# Power_Supply_LV.net
KiCad netlist of a schematic drawn in Altium Designer
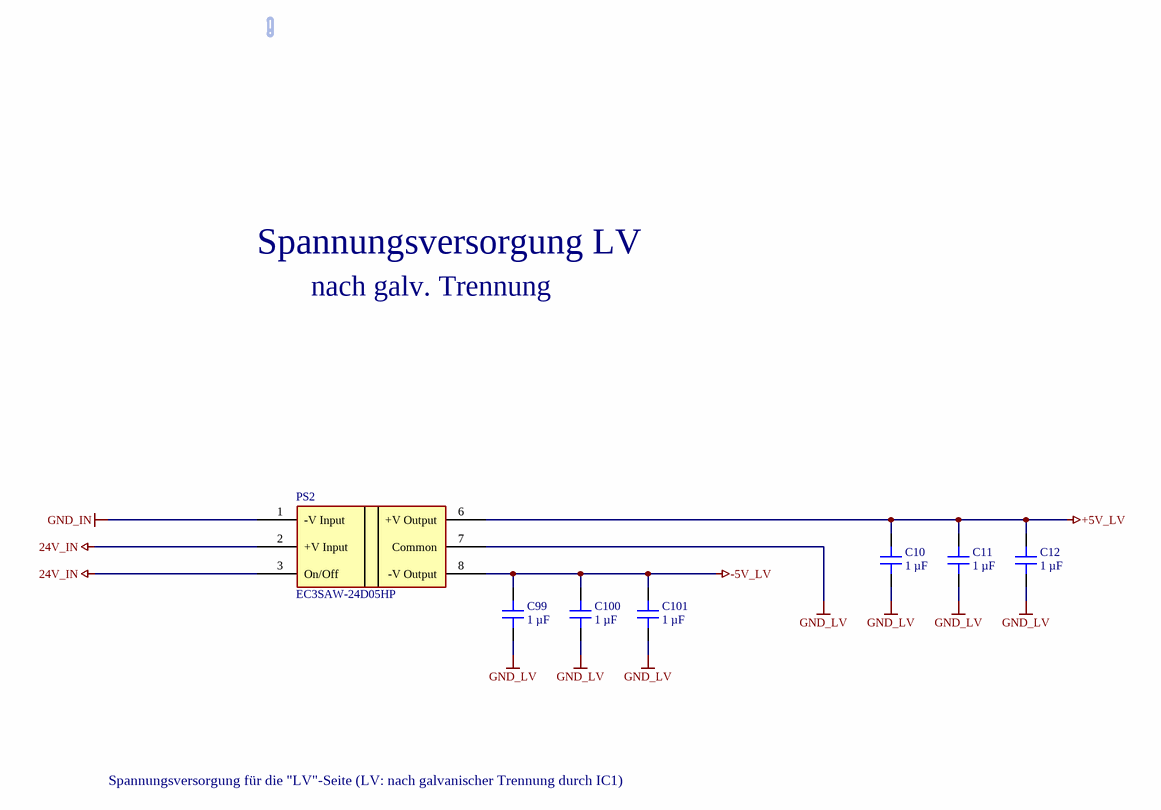
[diagram p0: Power_Supply_LV.SchDoc]

(export (version "E")
  (design (tool "Eeschema 10.0.6"))
  (components
    (comp (ref "C10")
      (value "1 µF")
      (footprint "C_0603")
      (description "50V 1uF X5R ±10% 0603  Multilayer Ceramic Capacitors MLCC - SMD/SMT ROHS")
      (fields
        (field (name "MANUFACTURER") "Samsung Electro-Mechanics")
        (field (name "MANUFACTURER PART NUMBER") "CL10A105KB8NNNC")
        (field (name "CREATED FROM") "MGremer")
      )
      (libsource (lib "user") (part "Capacitor"))
    )
    (comp (ref "C11")
      (value "1 µF")
      (footprint "C_0603")
      (description "50V 1uF X5R ±10% 0603  Multilayer Ceramic Capacitors MLCC - SMD/SMT ROHS")
      (fields
        (field (name "MANUFACTURER") "Samsung Electro-Mechanics")
        (field (name "MANUFACTURER PART NUMBER") "CL10A105KB8NNNC")
        (field (name "CREATED FROM") "MGremer")
      )
      (libsource (lib "user") (part "Capacitor"))
    )
    (comp (ref "C12")
      (value "1 µF")
      (footprint "C_0603")
      (description "50V 1uF X5R ±10% 0603  Multilayer Ceramic Capacitors MLCC - SMD/SMT ROHS")
      (fields
        (field (name "MANUFACTURER") "Samsung Electro-Mechanics")
        (field (name "MANUFACTURER PART NUMBER") "CL10A105KB8NNNC")
        (field (name "CREATED FROM") "MGremer")
      )
      (libsource (lib "user") (part "Capacitor"))
    )
    (comp (ref "C99")
      (value "1 µF")
      (footprint "C_0603")
      (description "50V 1uF X5R ±10% 0603  Multilayer Ceramic Capacitors MLCC - SMD/SMT ROHS")
      (fields
        (field (name "MANUFACTURER") "Samsung Electro-Mechanics")
        (field (name "MANUFACTURER PART NUMBER") "CL10A105KB8NNNC")
        (field (name "CREATED FROM") "MGremer")
      )
      (libsource (lib "user") (part "Capacitor"))
    )
    (comp (ref "C100")
      (value "1 µF")
      (footprint "C_0603")
      (description "50V 1uF X5R ±10% 0603  Multilayer Ceramic Capacitors MLCC - SMD/SMT ROHS")
      (fields
        (field (name "MANUFACTURER") "Samsung Electro-Mechanics")
        (field (name "MANUFACTURER PART NUMBER") "CL10A105KB8NNNC")
        (field (name "CREATED FROM") "MGremer")
      )
      (libsource (lib "user") (part "Capacitor"))
    )
    (comp (ref "C101")
      (value "1 µF")
      (footprint "C_0603")
      (description "50V 1uF X5R ±10% 0603  Multilayer Ceramic Capacitors MLCC - SMD/SMT ROHS")
      (fields
        (field (name "MANUFACTURER") "Samsung Electro-Mechanics")
        (field (name "MANUFACTURER PART NUMBER") "CL10A105KB8NNNC")
        (field (name "CREATED FROM") "MGremer")
      )
      (libsource (lib "user") (part "Capacitor"))
    )
    (comp (ref "PS2")
      (value "EC3SAW-24D05HP")
      (footprint "SamacSys:EC3SAW")
      (description "Isolierte DC/DC-Wandler – Durchsteckmontage 3W 9-36Vin +/-5Vout 300mA")
      (fields (field (name "MANUFACTURER") "Cincon"))
      (libsource (lib "SamacSys") (part "EC3SAW-24D05HP"))
    )
  )
  (nets
    (net (code "1") (name "+5V_LV") (class "Default")
      (node (ref "C10") (pin "2") (pinfunction "2_2") (pintype "passive"))
      (node (ref "C11") (pin "2") (pinfunction "2_2") (pintype "passive"))
      (node (ref "C12") (pin "2") (pinfunction "2_2") (pintype "passive"))
      (node (ref "PS2") (pin "6") (pinfunction "+V_Output_6") (pintype "power_in"))
    )
    (net (code "2") (name "-5V_LV") (class "Default")
      (node (ref "C100") (pin "2") (pinfunction "2_2") (pintype "passive"))
      (node (ref "C101") (pin "2") (pinfunction "2_2") (pintype "passive"))
      (node (ref "C99") (pin "2") (pinfunction "2_2") (pintype "passive"))
      (node (ref "PS2") (pin "8") (pinfunction "-V_Output_8") (pintype "power_in"))
    )
    (net (code "3") (name "24V_IN") (class "Default")
      (node (ref "PS2") (pin "2") (pinfunction "+V_Input_2") (pintype "power_in"))
      (node (ref "PS2") (pin "3") (pinfunction "On/Off_3") (pintype "passive"))
    )
    (net (code "4") (name "GND_IN") (class "Default")
      (node (ref "PS2") (pin "1") (pinfunction "-V_Input_1") (pintype "power_in"))
    )
    (net (code "5") (name "GND_LV") (class "Default")
      (node (ref "C10") (pin "1") (pinfunction "1_1") (pintype "passive"))
      (node (ref "C100") (pin "1") (pinfunction "1_1") (pintype "passive"))
      (node (ref "C101") (pin "1") (pinfunction "1_1") (pintype "passive"))
      (node (ref "C11") (pin "1") (pinfunction "1_1") (pintype "passive"))
      (node (ref "C12") (pin "1") (pinfunction "1_1") (pintype "passive"))
      (node (ref "C99") (pin "1") (pinfunction "1_1") (pintype "passive"))
      (node (ref "PS2") (pin "7") (pinfunction "Common_7") (pintype "power_in"))
    )
  )
)
